# V2_aktuell_StdTeile_panel.net
KiCad netlist of a schematic drawn in EAGLE
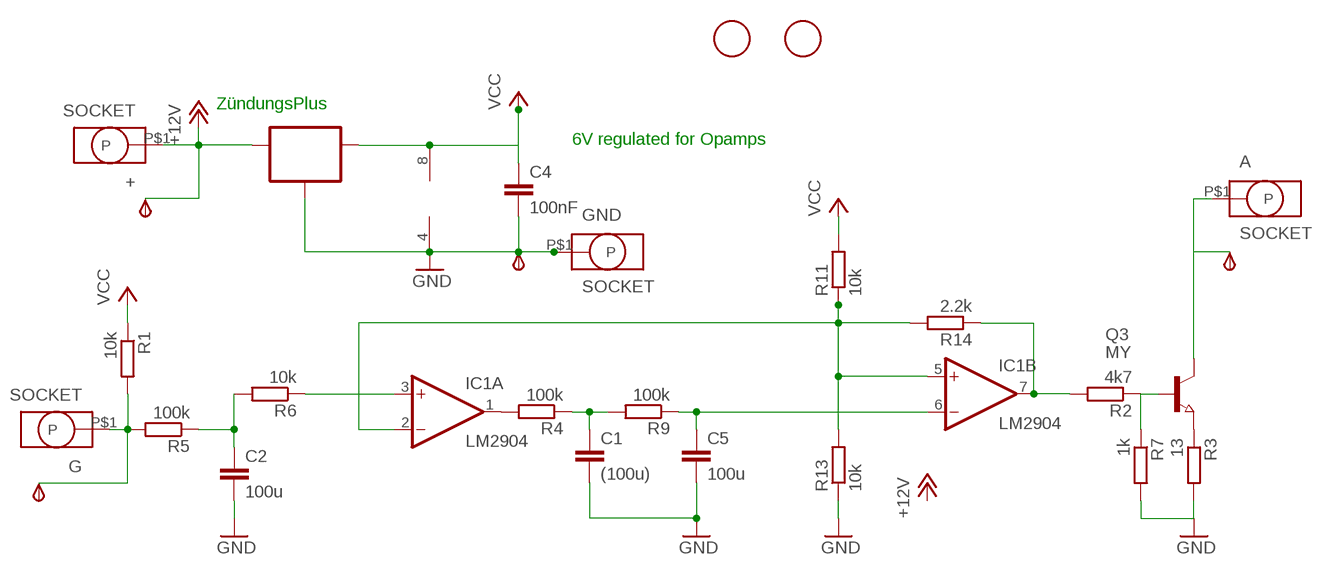
[diagram p0: schematic, sheet 1]
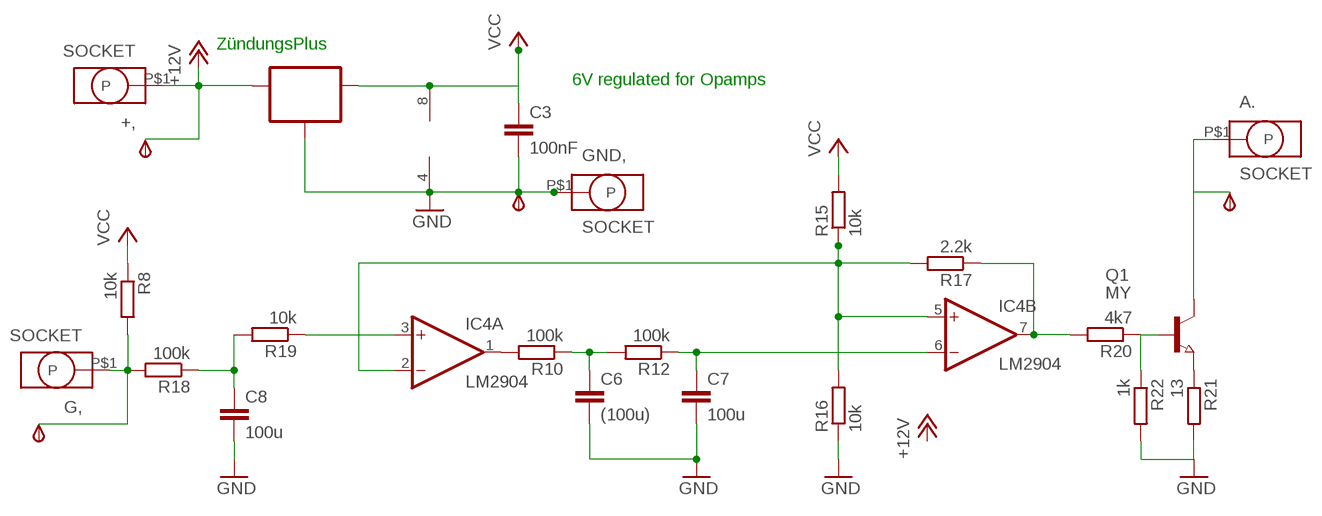
[diagram p1: schematic, sheet 2]
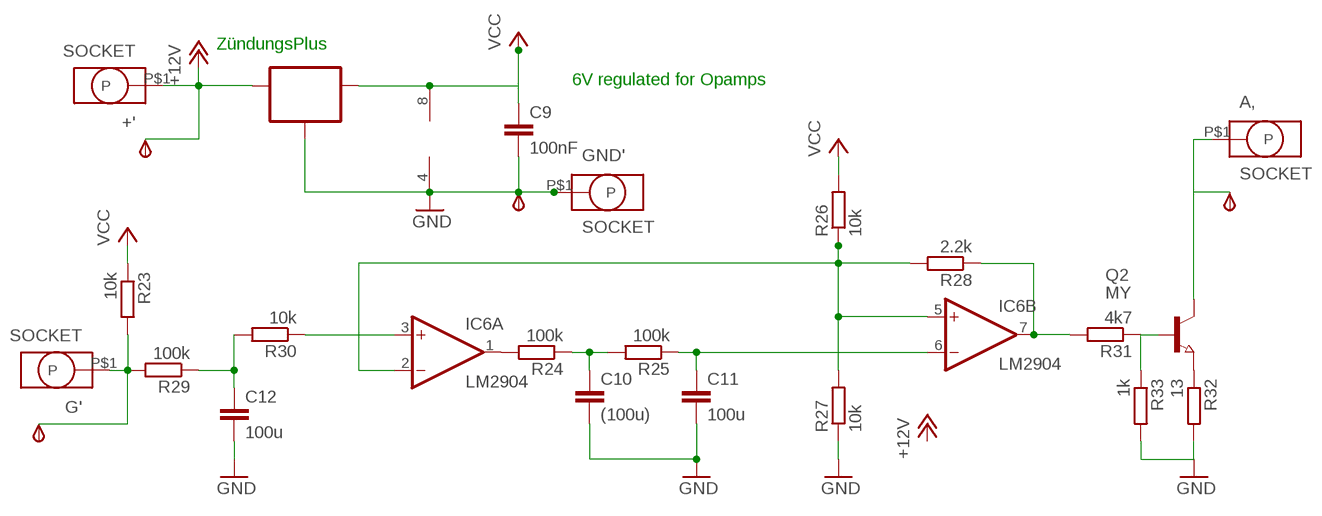
[diagram p2: schematic, sheet 3]
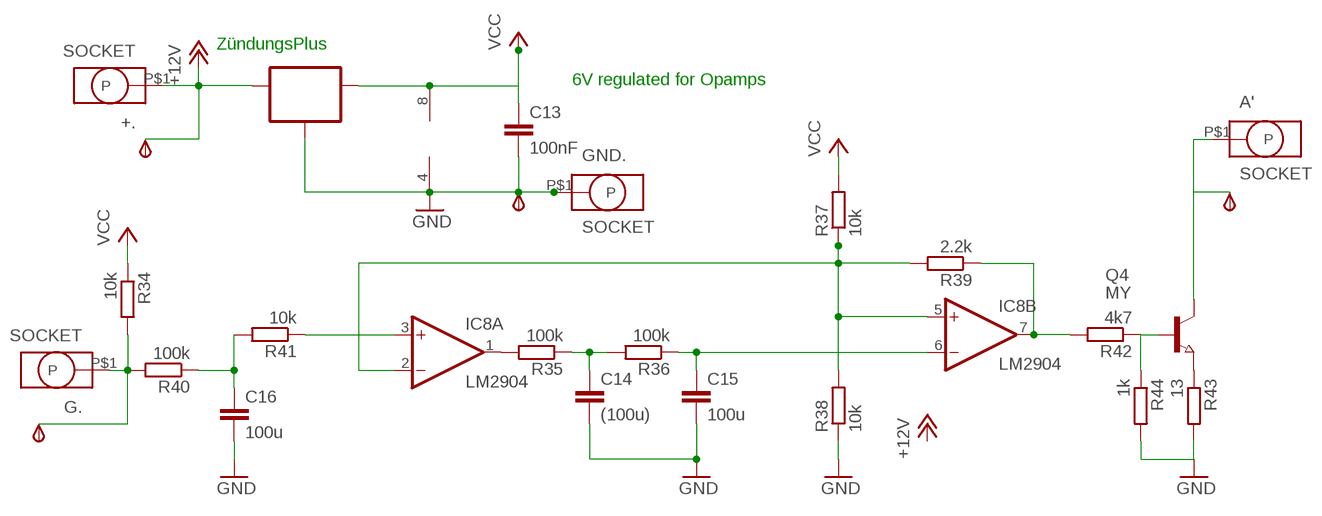
[diagram p3: schematic, sheet 4]

(export (version "E")
  (design (tool "Eeschema 10.0.6"))
  (components
    (comp (ref "+,")
      (value "SOCKET")
      (footprint "eagle-import:ID2.5MM")
      (libsource (lib "eagle-import") (part "SOCKET"))
    )
    (comp (ref "A.")
      (value "SOCKET")
      (footprint "eagle-import:ID2.5MM")
      (libsource (lib "eagle-import") (part "SOCKET"))
    )
    (comp (ref "C3")
      (value "100nF")
      (footprint "eagle-import:C0805")
      (libsource (lib "eagle-import") (part "C-EUC0805"))
    )
    (comp (ref "C6")
      (value "(100u)")
      (footprint "eagle-import:C1206K")
      (libsource (lib "eagle-import") (part "C-EUC1206K"))
    )
    (comp (ref "C7")
      (value "100u")
      (footprint "eagle-import:C1206K")
      (libsource (lib "eagle-import") (part "C-EUC1206K"))
    )
    (comp (ref "C8")
      (value "100u")
      (footprint "eagle-import:C1206K")
      (libsource (lib "eagle-import") (part "C-EUC1206K"))
    )
    (comp (ref "G,")
      (value "SOCKET")
      (footprint "eagle-import:ID2.5MM")
      (libsource (lib "eagle-import") (part "SOCKET"))
    )
    (comp (ref "GND,")
      (value "SOCKET")
      (footprint "eagle-import:ID2.5MM")
      (libsource (lib "eagle-import") (part "SOCKET"))
    )
    (comp (ref "GND_1")
      (value "TPSB2.0")
      (footprint "eagle-import:B2.0")
      (libsource (lib "eagle-import") (part "TPSB2.0"))
    )
    (comp (ref "IC3")
      (value "70L06")
      (footprint "eagle-import:SOT89_ROUND")
      (libsource (lib "eagle-import") (part "78LXXSOT89_ROUND"))
    )
    (comp (ref "IC4")
      (value "LM2904")
      (footprint "eagle-import:SO08")
      (libsource (lib "eagle-import") (part "LM358D"))
    )
    (comp (ref "IN,")
      (value "TPSB2.0")
      (footprint "eagle-import:B2.0")
      (libsource (lib "eagle-import") (part "TPSB2.0"))
    )
    (comp (ref "OUT.")
      (value "TPSB2.0")
      (footprint "eagle-import:B2.0")
      (libsource (lib "eagle-import") (part "TPSB2.0"))
    )
    (comp (ref "Q1")
      (value "MY")
      (footprint "eagle-import:SOT89")
      (libsource (lib "eagle-import") (part "NPN-TRANSISTOR_SOT89"))
    )
    (comp (ref "R8")
      (value "10k")
      (footprint "eagle-import:R0805")
      (libsource (lib "eagle-import") (part "R-EU_R0805"))
    )
    (comp (ref "R10")
      (value "100k")
      (footprint "eagle-import:R0805")
      (libsource (lib "eagle-import") (part "R-EU_R0805"))
    )
    (comp (ref "R12")
      (value "100k")
      (footprint "eagle-import:R0805")
      (libsource (lib "eagle-import") (part "R-EU_R0805"))
    )
    (comp (ref "R15")
      (value "10k")
      (footprint "eagle-import:R0805")
      (libsource (lib "eagle-import") (part "R-EU_R0805"))
    )
    (comp (ref "R16")
      (value "10k")
      (footprint "eagle-import:R0805")
      (libsource (lib "eagle-import") (part "R-EU_R0805"))
    )
    (comp (ref "R17")
      (value "2.2k")
      (footprint "eagle-import:R0805")
      (libsource (lib "eagle-import") (part "R-EU_R0805"))
    )
    (comp (ref "R18")
      (value "100k")
      (footprint "eagle-import:R0805")
      (libsource (lib "eagle-import") (part "R-EU_R0805"))
    )
    (comp (ref "R19")
      (value "10k")
      (footprint "eagle-import:R0805")
      (libsource (lib "eagle-import") (part "R-EU_R0805"))
    )
    (comp (ref "R20")
      (value "4k7")
      (footprint "eagle-import:R0805")
      (libsource (lib "eagle-import") (part "R-EU_R0805"))
    )
    (comp (ref "R21")
      (value "13")
      (footprint "eagle-import:R1206")
      (libsource (lib "eagle-import") (part "R-EU_R1206"))
    )
    (comp (ref "R22")
      (value "1k")
      (footprint "eagle-import:R0805")
      (libsource (lib "eagle-import") (part "R-EU_R0805"))
    )
    (comp (ref "V+,")
      (value "TPSB2.0")
      (footprint "eagle-import:B2.0")
      (libsource (lib "eagle-import") (part "TPSB2.0"))
    )
    (comp (ref "+.")
      (value "SOCKET")
      (footprint "eagle-import:ID2.5MM")
      (libsource (lib "eagle-import") (part "SOCKET"))
    )
    (comp (ref "A'")
      (value "SOCKET")
      (footprint "eagle-import:ID2.5MM")
      (libsource (lib "eagle-import") (part "SOCKET"))
    )
    (comp (ref "C13")
      (value "100nF")
      (footprint "eagle-import:C0805")
      (libsource (lib "eagle-import") (part "C-EUC0805"))
    )
    (comp (ref "C14")
      (value "(100u)")
      (footprint "eagle-import:C1206K")
      (libsource (lib "eagle-import") (part "C-EUC1206K"))
    )
    (comp (ref "C15")
      (value "100u")
      (footprint "eagle-import:C1206K")
      (libsource (lib "eagle-import") (part "C-EUC1206K"))
    )
    (comp (ref "C16")
      (value "100u")
      (footprint "eagle-import:C1206K")
      (libsource (lib "eagle-import") (part "C-EUC1206K"))
    )
    (comp (ref "G.")
      (value "SOCKET")
      (footprint "eagle-import:ID2.5MM")
      (libsource (lib "eagle-import") (part "SOCKET"))
    )
    (comp (ref "GND.")
      (value "SOCKET")
      (footprint "eagle-import:ID2.5MM")
      (libsource (lib "eagle-import") (part "SOCKET"))
    )
    (comp (ref "GND_3")
      (value "TPSB2.0")
      (footprint "eagle-import:B2.0")
      (libsource (lib "eagle-import") (part "TPSB2.0"))
    )
    (comp (ref "IC7")
      (value "70L06")
      (footprint "eagle-import:SOT89_ROUND")
      (libsource (lib "eagle-import") (part "78LXXSOT89_ROUND"))
    )
    (comp (ref "IC8")
      (value "LM2904")
      (footprint "eagle-import:SO08")
      (libsource (lib "eagle-import") (part "LM358D"))
    )
    (comp (ref "IN'")
      (value "TPSB2.0")
      (footprint "eagle-import:B2.0")
      (libsource (lib "eagle-import") (part "TPSB2.0"))
    )
    (comp (ref "OUT,")
      (value "TPSB2.0")
      (footprint "eagle-import:B2.0")
      (libsource (lib "eagle-import") (part "TPSB2.0"))
    )
    (comp (ref "Q4")
      (value "MY")
      (footprint "eagle-import:SOT89")
      (libsource (lib "eagle-import") (part "NPN-TRANSISTOR_SOT89"))
    )
    (comp (ref "R34")
      (value "10k")
      (footprint "eagle-import:R0805")
      (libsource (lib "eagle-import") (part "R-EU_R0805"))
    )
    (comp (ref "R35")
      (value "100k")
      (footprint "eagle-import:R0805")
      (libsource (lib "eagle-import") (part "R-EU_R0805"))
    )
    (comp (ref "R36")
      (value "100k")
      (footprint "eagle-import:R0805")
      (libsource (lib "eagle-import") (part "R-EU_R0805"))
    )
    (comp (ref "R37")
      (value "10k")
      (footprint "eagle-import:R0805")
      (libsource (lib "eagle-import") (part "R-EU_R0805"))
    )
    (comp (ref "R38")
      (value "10k")
      (footprint "eagle-import:R0805")
      (libsource (lib "eagle-import") (part "R-EU_R0805"))
    )
    (comp (ref "R39")
      (value "2.2k")
      (footprint "eagle-import:R0805")
      (libsource (lib "eagle-import") (part "R-EU_R0805"))
    )
    (comp (ref "R40")
      (value "100k")
      (footprint "eagle-import:R0805")
      (libsource (lib "eagle-import") (part "R-EU_R0805"))
    )
    (comp (ref "R41")
      (value "10k")
      (footprint "eagle-import:R0805")
      (libsource (lib "eagle-import") (part "R-EU_R0805"))
    )
    (comp (ref "R42")
      (value "4k7")
      (footprint "eagle-import:R0805")
      (libsource (lib "eagle-import") (part "R-EU_R0805"))
    )
    (comp (ref "R43")
      (value "13")
      (footprint "eagle-import:R1206")
      (libsource (lib "eagle-import") (part "R-EU_R1206"))
    )
    (comp (ref "R44")
      (value "1k")
      (footprint "eagle-import:R0805")
      (libsource (lib "eagle-import") (part "R-EU_R0805"))
    )
    (comp (ref "V+'")
      (value "TPSB2.0")
      (footprint "eagle-import:B2.0")
      (libsource (lib "eagle-import") (part "TPSB2.0"))
    )
    (comp (ref "+'")
      (value "SOCKET")
      (footprint "eagle-import:ID2.5MM")
      (libsource (lib "eagle-import") (part "SOCKET"))
    )
    (comp (ref "A,")
      (value "SOCKET")
      (footprint "eagle-import:ID2.5MM")
      (libsource (lib "eagle-import") (part "SOCKET"))
    )
    (comp (ref "C9")
      (value "100nF")
      (footprint "eagle-import:C0805")
      (libsource (lib "eagle-import") (part "C-EUC0805"))
    )
    (comp (ref "C10")
      (value "(100u)")
      (footprint "eagle-import:C1206K")
      (libsource (lib "eagle-import") (part "C-EUC1206K"))
    )
    (comp (ref "C11")
      (value "100u")
      (footprint "eagle-import:C1206K")
      (libsource (lib "eagle-import") (part "C-EUC1206K"))
    )
    (comp (ref "C12")
      (value "100u")
      (footprint "eagle-import:C1206K")
      (libsource (lib "eagle-import") (part "C-EUC1206K"))
    )
    (comp (ref "G'")
      (value "SOCKET")
      (footprint "eagle-import:ID2.5MM")
      (libsource (lib "eagle-import") (part "SOCKET"))
    )
    (comp (ref "GND'")
      (value "SOCKET")
      (footprint "eagle-import:ID2.5MM")
      (libsource (lib "eagle-import") (part "SOCKET"))
    )
    (comp (ref "GND_2")
      (value "TPSB2.0")
      (footprint "eagle-import:B2.0")
      (libsource (lib "eagle-import") (part "TPSB2.0"))
    )
    (comp (ref "IC5")
      (value "70L06")
      (footprint "eagle-import:SOT89_ROUND")
      (libsource (lib "eagle-import") (part "78LXXSOT89_ROUND"))
    )
    (comp (ref "IC6")
      (value "LM2904")
      (footprint "eagle-import:SO08")
      (libsource (lib "eagle-import") (part "LM358D"))
    )
    (comp (ref "IN.")
      (value "TPSB2.0")
      (footprint "eagle-import:B2.0")
      (libsource (lib "eagle-import") (part "TPSB2.0"))
    )
    (comp (ref "OUT'")
      (value "TPSB2.0")
      (footprint "eagle-import:B2.0")
      (libsource (lib "eagle-import") (part "TPSB2.0"))
    )
    (comp (ref "Q2")
      (value "MY")
      (footprint "eagle-import:SOT89")
      (libsource (lib "eagle-import") (part "NPN-TRANSISTOR_SOT89"))
    )
    (comp (ref "R23")
      (value "10k")
      (footprint "eagle-import:R0805")
      (libsource (lib "eagle-import") (part "R-EU_R0805"))
    )
    (comp (ref "R24")
      (value "100k")
      (footprint "eagle-import:R0805")
      (libsource (lib "eagle-import") (part "R-EU_R0805"))
    )
    (comp (ref "R25")
      (value "100k")
      (footprint "eagle-import:R0805")
      (libsource (lib "eagle-import") (part "R-EU_R0805"))
    )
    (comp (ref "R26")
      (value "10k")
      (footprint "eagle-import:R0805")
      (libsource (lib "eagle-import") (part "R-EU_R0805"))
    )
    (comp (ref "R27")
      (value "10k")
      (footprint "eagle-import:R0805")
      (libsource (lib "eagle-import") (part "R-EU_R0805"))
    )
    (comp (ref "R28")
      (value "2.2k")
      (footprint "eagle-import:R0805")
      (libsource (lib "eagle-import") (part "R-EU_R0805"))
    )
    (comp (ref "R29")
      (value "100k")
      (footprint "eagle-import:R0805")
      (libsource (lib "eagle-import") (part "R-EU_R0805"))
    )
    (comp (ref "R30")
      (value "10k")
      (footprint "eagle-import:R0805")
      (libsource (lib "eagle-import") (part "R-EU_R0805"))
    )
    (comp (ref "R31")
      (value "4k7")
      (footprint "eagle-import:R0805")
      (libsource (lib "eagle-import") (part "R-EU_R0805"))
    )
    (comp (ref "R32")
      (value "13")
      (footprint "eagle-import:R1206")
      (libsource (lib "eagle-import") (part "R-EU_R1206"))
    )
    (comp (ref "R33")
      (value "1k")
      (footprint "eagle-import:R0805")
      (libsource (lib "eagle-import") (part "R-EU_R0805"))
    )
    (comp (ref "V+.")
      (value "TPSB2.0")
      (footprint "eagle-import:B2.0")
      (libsource (lib "eagle-import") (part "TPSB2.0"))
    )
    (comp (ref "+")
      (value "SOCKET")
      (footprint "eagle-import:ID2.5MM")
      (libsource (lib "eagle-import") (part "SOCKET"))
    )
    (comp (ref "A")
      (value "SOCKET")
      (footprint "eagle-import:ID2.5MM")
      (libsource (lib "eagle-import") (part "SOCKET"))
    )
    (comp (ref "C1")
      (value "(100u)")
      (footprint "eagle-import:C1206K")
      (libsource (lib "eagle-import") (part "C-EUC1206K"))
    )
    (comp (ref "C2")
      (value "100u")
      (footprint "eagle-import:C1206K")
      (libsource (lib "eagle-import") (part "C-EUC1206K"))
    )
    (comp (ref "C4")
      (value "100nF")
      (footprint "eagle-import:C0805")
      (libsource (lib "eagle-import") (part "C-EUC0805"))
    )
    (comp (ref "C5")
      (value "100u")
      (footprint "eagle-import:C1206K")
      (libsource (lib "eagle-import") (part "C-EUC1206K"))
    )
    (comp (ref "G")
      (value "SOCKET")
      (footprint "eagle-import:ID2.5MM")
      (libsource (lib "eagle-import") (part "SOCKET"))
    )
    (comp (ref "GND")
      (value "SOCKET")
      (footprint "eagle-import:ID2.5MM")
      (libsource (lib "eagle-import") (part "SOCKET"))
    )
    (comp (ref "GND_")
      (value "TPSB2.0")
      (footprint "eagle-import:B2.0")
      (libsource (lib "eagle-import") (part "TPSB2.0"))
    )
    (comp (ref "IC1")
      (value "LM2904")
      (footprint "eagle-import:SO08")
      (libsource (lib "eagle-import") (part "LM358D"))
    )
    (comp (ref "IC2")
      (value "70L06")
      (footprint "eagle-import:SOT89_ROUND")
      (libsource (lib "eagle-import") (part "78LXXSOT89_ROUND"))
    )
    (comp (ref "IN")
      (value "TPSB2.0")
      (footprint "eagle-import:B2.0")
      (libsource (lib "eagle-import") (part "TPSB2.0"))
    )
    (comp (ref "OUT")
      (value "TPSB2.0")
      (footprint "eagle-import:B2.0")
      (libsource (lib "eagle-import") (part "TPSB2.0"))
    )
    (comp (ref "Q3")
      (value "MY")
      (footprint "eagle-import:SOT89")
      (libsource (lib "eagle-import") (part "NPN-TRANSISTOR_SOT89"))
    )
    (comp (ref "R1")
      (value "10k")
      (footprint "eagle-import:R0805")
      (libsource (lib "eagle-import") (part "R-EU_R0805"))
    )
    (comp (ref "R2")
      (value "4k7")
      (footprint "eagle-import:R0805")
      (libsource (lib "eagle-import") (part "R-EU_R0805"))
    )
    (comp (ref "R3")
      (value "13")
      (footprint "eagle-import:R1206")
      (libsource (lib "eagle-import") (part "R-EU_R1206"))
    )
    (comp (ref "R4")
      (value "100k")
      (footprint "eagle-import:R0805")
      (libsource (lib "eagle-import") (part "R-EU_R0805"))
    )
    (comp (ref "R5")
      (value "100k")
      (footprint "eagle-import:R0805")
      (libsource (lib "eagle-import") (part "R-EU_R0805"))
    )
    (comp (ref "R6")
      (value "10k")
      (footprint "eagle-import:R0805")
      (libsource (lib "eagle-import") (part "R-EU_R0805"))
    )
    (comp (ref "R7")
      (value "1k")
      (footprint "eagle-import:R0805")
      (libsource (lib "eagle-import") (part "R-EU_R0805"))
    )
    (comp (ref "R9")
      (value "100k")
      (footprint "eagle-import:R0805")
      (libsource (lib "eagle-import") (part "R-EU_R0805"))
    )
    (comp (ref "R11")
      (value "10k")
      (footprint "eagle-import:R0805")
      (libsource (lib "eagle-import") (part "R-EU_R0805"))
    )
    (comp (ref "R13")
      (value "10k")
      (footprint "eagle-import:R0805")
      (libsource (lib "eagle-import") (part "R-EU_R0805"))
    )
    (comp (ref "R14")
      (value "2.2k")
      (footprint "eagle-import:R0805")
      (libsource (lib "eagle-import") (part "R-EU_R0805"))
    )
    (comp (ref "U$1")
      (value "FIDUCIALFIDUCIAL_1MM_WITH_SOLDERMASK")
      (footprint "eagle-import:FIDUCIAL_1MM_WITH_SOLDERMASK")
      (libsource (lib "eagle-import") (part "FIDUCIALFIDUCIAL_1MM_WITH_SOLDERMASK"))
    )
    (comp (ref "U$2")
      (value "FIDUCIALFIDUCIAL_1MM_WITH_SOLDERMASK")
      (footprint "eagle-import:FIDUCIAL_1MM_WITH_SOLDERMASK")
      (libsource (lib "eagle-import") (part "FIDUCIALFIDUCIAL_1MM_WITH_SOLDERMASK"))
    )
    (comp (ref "V+")
      (value "TPSB2.0")
      (footprint "eagle-import:B2.0")
      (libsource (lib "eagle-import") (part "TPSB2.0"))
    )
  )
  (nets
    (net (code "1") (name "+12V") (class "Default")
      (node (ref "+") (pin "P$1") (pinfunction "P_P$1") (pintype "bidirectional"))
      (node (ref "+'") (pin "P$1") (pinfunction "P_P$1") (pintype "bidirectional"))
      (node (ref "+,") (pin "P$1") (pinfunction "P_P$1") (pintype "bidirectional"))
      (node (ref "+.") (pin "P$1") (pinfunction "P_P$1") (pintype "bidirectional"))
      (node (ref "IC2") (pin "3") (pinfunction "IN_3") (pintype "input"))
      (node (ref "IC3") (pin "3") (pinfunction "IN_3") (pintype "input"))
      (node (ref "IC5") (pin "3") (pinfunction "IN_3") (pintype "input"))
      (node (ref "IC7") (pin "3") (pinfunction "IN_3") (pintype "input"))
      (node (ref "V+") (pin "TP") (pinfunction "PP_TP") (pintype "input"))
      (node (ref "V+'") (pin "TP") (pinfunction "PP_TP") (pintype "input"))
      (node (ref "V+,") (pin "TP") (pinfunction "PP_TP") (pintype "input"))
      (node (ref "V+.") (pin "TP") (pinfunction "PP_TP") (pintype "input"))
    )
    (net (code "2") (name "GND") (class "Default")
      (node (ref "C1") (pin "2") (pinfunction "2_2") (pintype "passive"))
      (node (ref "C10") (pin "2") (pinfunction "2_2") (pintype "passive"))
      (node (ref "C11") (pin "2") (pinfunction "2_2") (pintype "passive"))
      (node (ref "C12") (pin "2") (pinfunction "2_2") (pintype "passive"))
      (node (ref "C13") (pin "2") (pinfunction "2_2") (pintype "passive"))
      (node (ref "C14") (pin "2") (pinfunction "2_2") (pintype "passive"))
      (node (ref "C15") (pin "2") (pinfunction "2_2") (pintype "passive"))
      (node (ref "C16") (pin "2") (pinfunction "2_2") (pintype "passive"))
      (node (ref "C2") (pin "2") (pinfunction "2_2") (pintype "passive"))
      (node (ref "C3") (pin "2") (pinfunction "2_2") (pintype "passive"))
      (node (ref "C4") (pin "2") (pinfunction "2_2") (pintype "passive"))
      (node (ref "C5") (pin "2") (pinfunction "2_2") (pintype "passive"))
      (node (ref "C6") (pin "2") (pinfunction "2_2") (pintype "passive"))
      (node (ref "C7") (pin "2") (pinfunction "2_2") (pintype "passive"))
      (node (ref "C8") (pin "2") (pinfunction "2_2") (pintype "passive"))
      (node (ref "C9") (pin "2") (pinfunction "2_2") (pintype "passive"))
      (node (ref "GND") (pin "P$1") (pinfunction "P_P$1") (pintype "bidirectional"))
      (node (ref "GND'") (pin "P$1") (pinfunction "P_P$1") (pintype "bidirectional"))
      (node (ref "GND,") (pin "P$1") (pinfunction "P_P$1") (pintype "bidirectional"))
      (node (ref "GND.") (pin "P$1") (pinfunction "P_P$1") (pintype "bidirectional"))
      (node (ref "GND_") (pin "TP") (pinfunction "PP_TP") (pintype "input"))
      (node (ref "GND_1") (pin "TP") (pinfunction "PP_TP") (pintype "input"))
      (node (ref "GND_2") (pin "TP") (pinfunction "PP_TP") (pintype "input"))
      (node (ref "GND_3") (pin "TP") (pinfunction "PP_TP") (pintype "input"))
      (node (ref "IC1") (pin "4") (pinfunction "V-_4") (pintype "power_in"))
      (node (ref "IC2") (pin "2") (pinfunction "GND_2") (pintype "input"))
      (node (ref "IC2") (pin "2@1") (pinfunction "GND_2@1") (pintype "input"))
      (node (ref "IC3") (pin "2") (pinfunction "GND_2") (pintype "input"))
      (node (ref "IC3") (pin "2@1") (pinfunction "GND_2@1") (pintype "input"))
      (node (ref "IC4") (pin "4") (pinfunction "V-_4") (pintype "power_in"))
      (node (ref "IC5") (pin "2") (pinfunction "GND_2") (pintype "input"))
      (node (ref "IC5") (pin "2@1") (pinfunction "GND_2@1") (pintype "input"))
      (node (ref "IC6") (pin "4") (pinfunction "V-_4") (pintype "power_in"))
      (node (ref "IC7") (pin "2") (pinfunction "GND_2") (pintype "input"))
      (node (ref "IC7") (pin "2@1") (pinfunction "GND_2@1") (pintype "input"))
      (node (ref "IC8") (pin "4") (pinfunction "V-_4") (pintype "power_in"))
      (node (ref "R13") (pin "1") (pinfunction "1_1") (pintype "passive"))
      (node (ref "R16") (pin "1") (pinfunction "1_1") (pintype "passive"))
      (node (ref "R21") (pin "2") (pinfunction "2_2") (pintype "passive"))
      (node (ref "R22") (pin "2") (pinfunction "2_2") (pintype "passive"))
      (node (ref "R27") (pin "1") (pinfunction "1_1") (pintype "passive"))
      (node (ref "R3") (pin "2") (pinfunction "2_2") (pintype "passive"))
      (node (ref "R32") (pin "2") (pinfunction "2_2") (pintype "passive"))
      (node (ref "R33") (pin "2") (pinfunction "2_2") (pintype "passive"))
      (node (ref "R38") (pin "1") (pinfunction "1_1") (pintype "passive"))
      (node (ref "R43") (pin "2") (pinfunction "2_2") (pintype "passive"))
      (node (ref "R44") (pin "2") (pinfunction "2_2") (pintype "passive"))
      (node (ref "R7") (pin "2") (pinfunction "2_2") (pintype "passive"))
    )
    (net (code "3") (name "Net-(A'-P)") (class "Default")
      (node (ref "A'") (pin "P$1") (pinfunction "P_P$1") (pintype "bidirectional"))
      (node (ref "OUT,") (pin "TP") (pinfunction "PP_TP") (pintype "input"))
      (node (ref "Q4") (pin "2") (pinfunction "C_2") (pintype "passive"))
    )
    (net (code "4") (name "Net-(A,-P)") (class "Default")
      (node (ref "A,") (pin "P$1") (pinfunction "P_P$1") (pintype "bidirectional"))
      (node (ref "OUT'") (pin "TP") (pinfunction "PP_TP") (pintype "input"))
      (node (ref "Q2") (pin "2") (pinfunction "C_2") (pintype "passive"))
    )
    (net (code "5") (name "Net-(A-P)") (class "Default")
      (node (ref "A") (pin "P$1") (pinfunction "P_P$1") (pintype "bidirectional"))
      (node (ref "OUT") (pin "TP") (pinfunction "PP_TP") (pintype "input"))
      (node (ref "Q3") (pin "2") (pinfunction "C_2") (pintype "passive"))
    )
    (net (code "6") (name "Net-(A.-P)") (class "Default")
      (node (ref "A.") (pin "P$1") (pinfunction "P_P$1") (pintype "bidirectional"))
      (node (ref "OUT.") (pin "TP") (pinfunction "PP_TP") (pintype "input"))
      (node (ref "Q1") (pin "2") (pinfunction "C_2") (pintype "passive"))
    )
    (net (code "7") (name "Net-(C1-Pad1)") (class "Default")
      (node (ref "C1") (pin "1") (pinfunction "1_1") (pintype "passive"))
      (node (ref "R4") (pin "1") (pinfunction "1_1") (pintype "passive"))
      (node (ref "R9") (pin "2") (pinfunction "2_2") (pintype "passive"))
    )
    (net (code "8") (name "Net-(C2-Pad1)") (class "Default")
      (node (ref "C2") (pin "1") (pinfunction "1_1") (pintype "passive"))
      (node (ref "R5") (pin "1") (pinfunction "1_1") (pintype "passive"))
      (node (ref "R6") (pin "2") (pinfunction "2_2") (pintype "passive"))
    )
    (net (code "9") (name "Net-(C6-Pad1)") (class "Default")
      (node (ref "C6") (pin "1") (pinfunction "1_1") (pintype "passive"))
      (node (ref "R10") (pin "1") (pinfunction "1_1") (pintype "passive"))
      (node (ref "R12") (pin "2") (pinfunction "2_2") (pintype "passive"))
    )
    (net (code "10") (name "Net-(C8-Pad1)") (class "Default")
      (node (ref "C8") (pin "1") (pinfunction "1_1") (pintype "passive"))
      (node (ref "R18") (pin "1") (pinfunction "1_1") (pintype "passive"))
      (node (ref "R19") (pin "2") (pinfunction "2_2") (pintype "passive"))
    )
    (net (code "11") (name "Net-(C10-Pad1)") (class "Default")
      (node (ref "C10") (pin "1") (pinfunction "1_1") (pintype "passive"))
      (node (ref "R24") (pin "1") (pinfunction "1_1") (pintype "passive"))
      (node (ref "R25") (pin "2") (pinfunction "2_2") (pintype "passive"))
    )
    (net (code "12") (name "Net-(C12-Pad1)") (class "Default")
      (node (ref "C12") (pin "1") (pinfunction "1_1") (pintype "passive"))
      (node (ref "R29") (pin "1") (pinfunction "1_1") (pintype "passive"))
      (node (ref "R30") (pin "2") (pinfunction "2_2") (pintype "passive"))
    )
    (net (code "13") (name "Net-(C14-Pad1)") (class "Default")
      (node (ref "C14") (pin "1") (pinfunction "1_1") (pintype "passive"))
      (node (ref "R35") (pin "1") (pinfunction "1_1") (pintype "passive"))
      (node (ref "R36") (pin "2") (pinfunction "2_2") (pintype "passive"))
    )
    (net (code "14") (name "Net-(C16-Pad1)") (class "Default")
      (node (ref "C16") (pin "1") (pinfunction "1_1") (pintype "passive"))
      (node (ref "R40") (pin "1") (pinfunction "1_1") (pintype "passive"))
      (node (ref "R41") (pin "2") (pinfunction "2_2") (pintype "passive"))
    )
    (net (code "15") (name "Net-(G'-P)") (class "Default")
      (node (ref "G'") (pin "P$1") (pinfunction "P_P$1") (pintype "bidirectional"))
      (node (ref "IN.") (pin "TP") (pinfunction "PP_TP") (pintype "input"))
      (node (ref "R23") (pin "2") (pinfunction "2_2") (pintype "passive"))
      (node (ref "R29") (pin "2") (pinfunction "2_2") (pintype "passive"))
    )
    (net (code "16") (name "Net-(G,-P)") (class "Default")
      (node (ref "G,") (pin "P$1") (pinfunction "P_P$1") (pintype "bidirectional"))
      (node (ref "IN,") (pin "TP") (pinfunction "PP_TP") (pintype "input"))
      (node (ref "R18") (pin "2") (pinfunction "2_2") (pintype "passive"))
      (node (ref "R8") (pin "2") (pinfunction "2_2") (pintype "passive"))
    )
    (net (code "17") (name "Net-(G-P)") (class "Default")
      (node (ref "G") (pin "P$1") (pinfunction "P_P$1") (pintype "bidirectional"))
      (node (ref "IN") (pin "TP") (pinfunction "PP_TP") (pintype "input"))
      (node (ref "R1") (pin "2") (pinfunction "2_2") (pintype "passive"))
      (node (ref "R5") (pin "2") (pinfunction "2_2") (pintype "passive"))
    )
    (net (code "18") (name "Net-(G.-P)") (class "Default")
      (node (ref "G.") (pin "P$1") (pinfunction "P_P$1") (pintype "bidirectional"))
      (node (ref "IN'") (pin "TP") (pinfunction "PP_TP") (pintype "input"))
      (node (ref "R34") (pin "2") (pinfunction "2_2") (pintype "passive"))
      (node (ref "R40") (pin "2") (pinfunction "2_2") (pintype "passive"))
    )
    (net (code "19") (name "Net-(IC1A-+IN)") (class "Default")
      (node (ref "IC1") (pin "3") (pinfunction "+IN_3") (pintype "input"))
      (node (ref "R6") (pin "1") (pinfunction "1_1") (pintype "passive"))
    )
    (net (code "20") (name "Net-(IC1A--IN)") (class "Default")
      (node (ref "IC1") (pin "2") (pinfunction "-IN_2") (pintype "input"))
      (node (ref "IC1") (pin "5") (pinfunction "+IN_5") (pintype "input"))
      (node (ref "R11") (pin "1") (pinfunction "1_1") (pintype "passive"))
      (node (ref "R13") (pin "2") (pinfunction "2_2") (pintype "passive"))
      (node (ref "R14") (pin "2") (pinfunction "2_2") (pintype "passive"))
    )
    (net (code "21") (name "Net-(IC1A-OUT)") (class "Default")
      (node (ref "IC1") (pin "1") (pinfunction "OUT_1") (pintype "output"))
      (node (ref "R4") (pin "2") (pinfunction "2_2") (pintype "passive"))
    )
    (net (code "22") (name "Net-(IC1B--IN)") (class "Default")
      (node (ref "C5") (pin "1") (pinfunction "1_1") (pintype "passive"))
      (node (ref "IC1") (pin "6") (pinfunction "-IN_6") (pintype "input"))
      (node (ref "R9") (pin "1") (pinfunction "1_1") (pintype "passive"))
    )
    (net (code "23") (name "Net-(IC1B-OUT)") (class "Default")
      (node (ref "IC1") (pin "7") (pinfunction "OUT_7") (pintype "output"))
      (node (ref "R14") (pin "1") (pinfunction "1_1") (pintype "passive"))
      (node (ref "R2") (pin "2") (pinfunction "2_2") (pintype "passive"))
    )
    (net (code "24") (name "Net-(IC4A-+IN)") (class "Default")
      (node (ref "IC4") (pin "3") (pinfunction "+IN_3") (pintype "input"))
      (node (ref "R19") (pin "1") (pinfunction "1_1") (pintype "passive"))
    )
    (net (code "25") (name "Net-(IC4A--IN)") (class "Default")
      (node (ref "IC4") (pin "2") (pinfunction "-IN_2") (pintype "input"))
      (node (ref "IC4") (pin "5") (pinfunction "+IN_5") (pintype "input"))
      (node (ref "R15") (pin "1") (pinfunction "1_1") (pintype "passive"))
      (node (ref "R16") (pin "2") (pinfunction "2_2") (pintype "passive"))
      (node (ref "R17") (pin "2") (pinfunction "2_2") (pintype "passive"))
    )
    (net (code "26") (name "Net-(IC4A-OUT)") (class "Default")
      (node (ref "IC4") (pin "1") (pinfunction "OUT_1") (pintype "output"))
      (node (ref "R10") (pin "2") (pinfunction "2_2") (pintype "passive"))
    )
    (net (code "27") (name "Net-(IC4B--IN)") (class "Default")
      (node (ref "C7") (pin "1") (pinfunction "1_1") (pintype "passive"))
      (node (ref "IC4") (pin "6") (pinfunction "-IN_6") (pintype "input"))
      (node (ref "R12") (pin "1") (pinfunction "1_1") (pintype "passive"))
    )
    (net (code "28") (name "Net-(IC4B-OUT)") (class "Default")
      (node (ref "IC4") (pin "7") (pinfunction "OUT_7") (pintype "output"))
      (node (ref "R17") (pin "1") (pinfunction "1_1") (pintype "passive"))
      (node (ref "R20") (pin "2") (pinfunction "2_2") (pintype "passive"))
    )
    (net (code "29") (name "Net-(IC6A-+IN)") (class "Default")
      (node (ref "IC6") (pin "3") (pinfunction "+IN_3") (pintype "input"))
      (node (ref "R30") (pin "1") (pinfunction "1_1") (pintype "passive"))
    )
    (net (code "30") (name "Net-(IC6A--IN)") (class "Default")
      (node (ref "IC6") (pin "2") (pinfunction "-IN_2") (pintype "input"))
      (node (ref "IC6") (pin "5") (pinfunction "+IN_5") (pintype "input"))
      (node (ref "R26") (pin "1") (pinfunction "1_1") (pintype "passive"))
      (node (ref "R27") (pin "2") (pinfunction "2_2") (pintype "passive"))
      (node (ref "R28") (pin "2") (pinfunction "2_2") (pintype "passive"))
    )
    (net (code "31") (name "Net-(IC6A-OUT)") (class "Default")
      (node (ref "IC6") (pin "1") (pinfunction "OUT_1") (pintype "output"))
      (node (ref "R24") (pin "2") (pinfunction "2_2") (pintype "passive"))
    )
    (net (code "32") (name "Net-(IC6B--IN)") (class "Default")
      (node (ref "C11") (pin "1") (pinfunction "1_1") (pintype "passive"))
      (node (ref "IC6") (pin "6") (pinfunction "-IN_6") (pintype "input"))
      (node (ref "R25") (pin "1") (pinfunction "1_1") (pintype "passive"))
    )
    (net (code "33") (name "Net-(IC6B-OUT)") (class "Default")
      (node (ref "IC6") (pin "7") (pinfunction "OUT_7") (pintype "output"))
      (node (ref "R28") (pin "1") (pinfunction "1_1") (pintype "passive"))
      (node (ref "R31") (pin "2") (pinfunction "2_2") (pintype "passive"))
    )
    (net (code "34") (name "Net-(IC8A-+IN)") (class "Default")
      (node (ref "IC8") (pin "3") (pinfunction "+IN_3") (pintype "input"))
      (node (ref "R41") (pin "1") (pinfunction "1_1") (pintype "passive"))
    )
    (net (code "35") (name "Net-(IC8A--IN)") (class "Default")
      (node (ref "IC8") (pin "2") (pinfunction "-IN_2") (pintype "input"))
      (node (ref "IC8") (pin "5") (pinfunction "+IN_5") (pintype "input"))
      (node (ref "R37") (pin "1") (pinfunction "1_1") (pintype "passive"))
      (node (ref "R38") (pin "2") (pinfunction "2_2") (pintype "passive"))
      (node (ref "R39") (pin "2") (pinfunction "2_2") (pintype "passive"))
    )
    (net (code "36") (name "Net-(IC8A-OUT)") (class "Default")
      (node (ref "IC8") (pin "1") (pinfunction "OUT_1") (pintype "output"))
      (node (ref "R35") (pin "2") (pinfunction "2_2") (pintype "passive"))
    )
    (net (code "37") (name "Net-(IC8B--IN)") (class "Default")
      (node (ref "C15") (pin "1") (pinfunction "1_1") (pintype "passive"))
      (node (ref "IC8") (pin "6") (pinfunction "-IN_6") (pintype "input"))
      (node (ref "R36") (pin "1") (pinfunction "1_1") (pintype "passive"))
    )
    (net (code "38") (name "Net-(IC8B-OUT)") (class "Default")
      (node (ref "IC8") (pin "7") (pinfunction "OUT_7") (pintype "output"))
      (node (ref "R39") (pin "1") (pinfunction "1_1") (pintype "passive"))
      (node (ref "R42") (pin "2") (pinfunction "2_2") (pintype "passive"))
    )
    (net (code "39") (name "Net-(Q1-B)") (class "Default")
      (node (ref "Q1") (pin "1") (pinfunction "B_1") (pintype "passive"))
      (node (ref "R20") (pin "1") (pinfunction "1_1") (pintype "passive"))
      (node (ref "R22") (pin "1") (pinfunction "1_1") (pintype "passive"))
    )
    (net (code "40") (name "Net-(Q1-E)") (class "Default")
      (node (ref "Q1") (pin "3") (pinfunction "E_3") (pintype "passive"))
      (node (ref "R21") (pin "1") (pinfunction "1_1") (pintype "passive"))
    )
    (net (code "41") (name "Net-(Q2-B)") (class "Default")
      (node (ref "Q2") (pin "1") (pinfunction "B_1") (pintype "passive"))
      (node (ref "R31") (pin "1") (pinfunction "1_1") (pintype "passive"))
      (node (ref "R33") (pin "1") (pinfunction "1_1") (pintype "passive"))
    )
    (net (code "42") (name "Net-(Q2-E)") (class "Default")
      (node (ref "Q2") (pin "3") (pinfunction "E_3") (pintype "passive"))
      (node (ref "R32") (pin "1") (pinfunction "1_1") (pintype "passive"))
    )
    (net (code "43") (name "Net-(Q3-B)") (class "Default")
      (node (ref "Q3") (pin "1") (pinfunction "B_1") (pintype "passive"))
      (node (ref "R2") (pin "1") (pinfunction "1_1") (pintype "passive"))
      (node (ref "R7") (pin "1") (pinfunction "1_1") (pintype "passive"))
    )
    (net (code "44") (name "Net-(Q3-E)") (class "Default")
      (node (ref "Q3") (pin "3") (pinfunction "E_3") (pintype "passive"))
      (node (ref "R3") (pin "1") (pinfunction "1_1") (pintype "passive"))
    )
    (net (code "45") (name "Net-(Q4-B)") (class "Default")
      (node (ref "Q4") (pin "1") (pinfunction "B_1") (pintype "passive"))
      (node (ref "R42") (pin "1") (pinfunction "1_1") (pintype "passive"))
      (node (ref "R44") (pin "1") (pinfunction "1_1") (pintype "passive"))
    )
    (net (code "46") (name "Net-(Q4-E)") (class "Default")
      (node (ref "Q4") (pin "3") (pinfunction "E_3") (pintype "passive"))
      (node (ref "R43") (pin "1") (pinfunction "1_1") (pintype "passive"))
    )
    (net (code "47") (name "VCC") (class "Default")
      (node (ref "C13") (pin "1") (pinfunction "1_1") (pintype "passive"))
      (node (ref "C3") (pin "1") (pinfunction "1_1") (pintype "passive"))
      (node (ref "C4") (pin "1") (pinfunction "1_1") (pintype "passive"))
      (node (ref "C9") (pin "1") (pinfunction "1_1") (pintype "passive"))
      (node (ref "IC1") (pin "8") (pinfunction "V+_8") (pintype "power_in"))
      (node (ref "IC2") (pin "1") (pinfunction "OUT_1") (pintype "passive"))
      (node (ref "IC3") (pin "1") (pinfunction "OUT_1") (pintype "passive"))
      (node (ref "IC4") (pin "8") (pinfunction "V+_8") (pintype "power_in"))
      (node (ref "IC5") (pin "1") (pinfunction "OUT_1") (pintype "passive"))
      (node (ref "IC6") (pin "8") (pinfunction "V+_8") (pintype "power_in"))
      (node (ref "IC7") (pin "1") (pinfunction "OUT_1") (pintype "passive"))
      (node (ref "IC8") (pin "8") (pinfunction "V+_8") (pintype "power_in"))
      (node (ref "R1") (pin "1") (pinfunction "1_1") (pintype "passive"))
      (node (ref "R11") (pin "2") (pinfunction "2_2") (pintype "passive"))
      (node (ref "R15") (pin "2") (pinfunction "2_2") (pintype "passive"))
      (node (ref "R23") (pin "1") (pinfunction "1_1") (pintype "passive"))
      (node (ref "R26") (pin "2") (pinfunction "2_2") (pintype "passive"))
      (node (ref "R34") (pin "1") (pinfunction "1_1") (pintype "passive"))
      (node (ref "R37") (pin "2") (pinfunction "2_2") (pintype "passive"))
      (node (ref "R8") (pin "1") (pinfunction "1_1") (pintype "passive"))
    )
  )
)
